# midi_transmitter.net
KiCad netlist of a schematic drawn in EAGLE
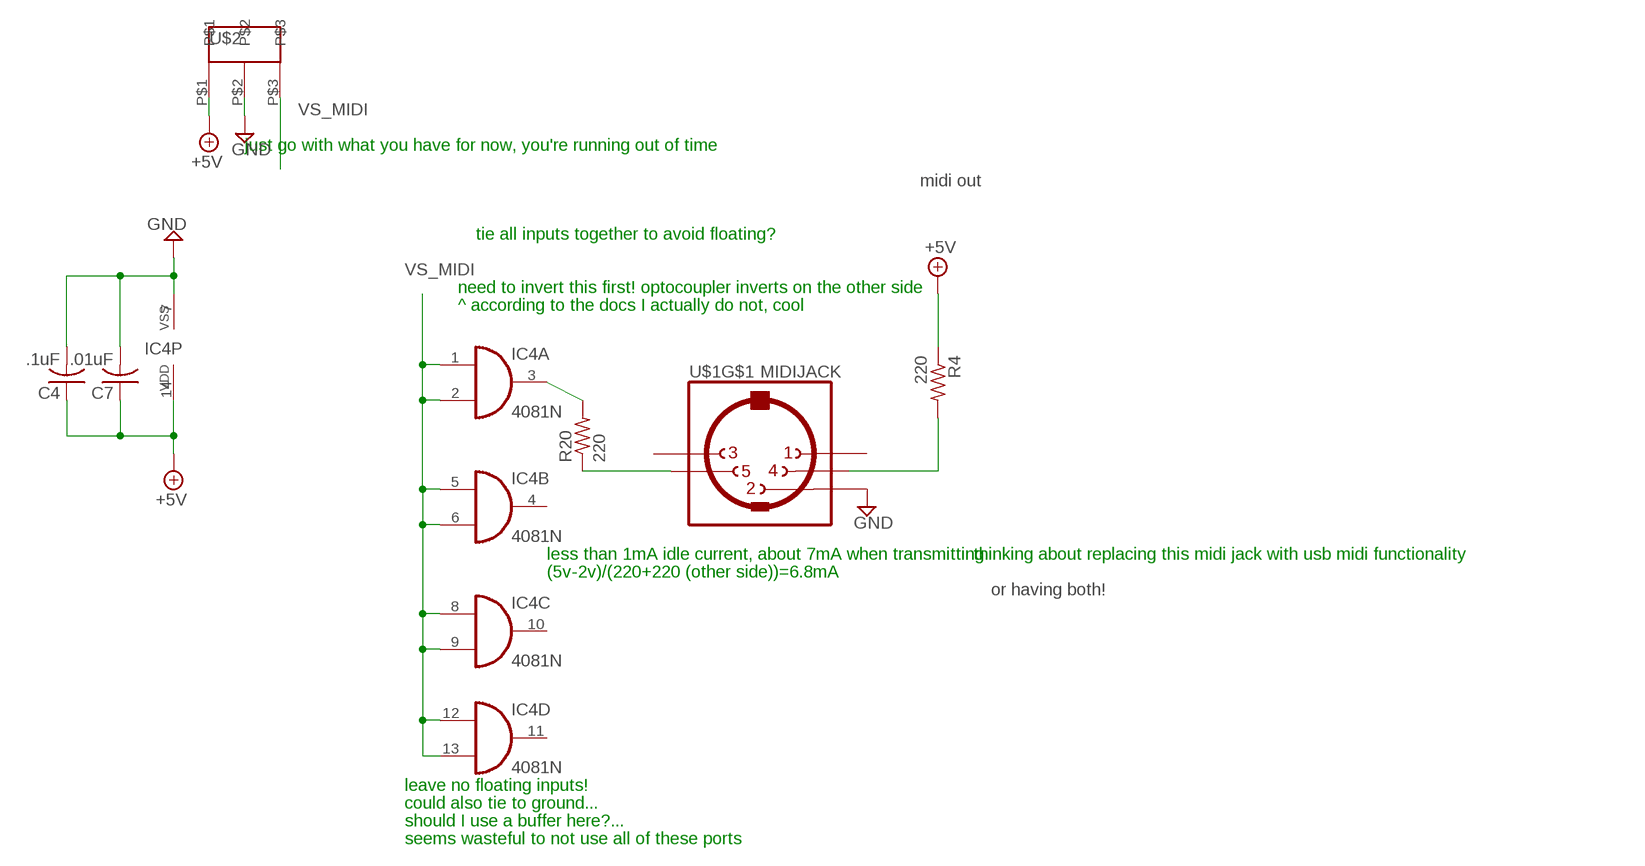
[diagram p0: schematic, sheet 1]

(export (version "E")
  (design (tool "Eeschema 10.0.6"))
  (components
    (comp (ref "C4")
      (value ".1uF")
      (footprint "eagle-import:C025-030X050")
      (libsource (lib "eagle-import") (part "C-US025-030X050"))
    )
    (comp (ref "C7")
      (value ".01uF")
      (footprint "eagle-import:C025-030X050")
      (libsource (lib "eagle-import") (part "C-US025-030X050"))
    )
    (comp (ref "IC4")
      (value "4081N")
      (footprint "eagle-import:DIL14")
      (fields (field (name "SPICEPREFIX") "J"))
      (libsource (lib "eagle-import") (part "4081N"))
    )
    (comp (ref "R4")
      (value "220")
      (footprint "eagle-import:0204_7")
      (libsource (lib "eagle-import") (part "R-US_0204/7"))
    )
    (comp (ref "R20")
      (value "220")
      (footprint "eagle-import:0204_7")
      (libsource (lib "eagle-import") (part "R-US_0204/7"))
    )
    (comp (ref "U$1")
      (value "MIDIJACK")
      (footprint "eagle-import:CP-2350")
      (libsource (lib "eagle-import") (part "MIDIJACK"))
    )
    (comp (ref "U$2")
      (value "3-PIN-HEADER")
      (footprint "eagle-import:3-PIN-HEADER")
      (libsource (lib "eagle-import") (part "3-PIN-HEADER"))
    )
  )
  (nets
    (net (code "1") (name "+5V") (class "Default")
      (node (ref "C4") (pin "1") (pinfunction "1_1") (pintype "passive"))
      (node (ref "C7") (pin "1") (pinfunction "1_1") (pintype "passive"))
      (node (ref "IC4") (pin "14") (pinfunction "VDD_14") (pintype "power_in"))
      (node (ref "R4") (pin "1") (pinfunction "1_1") (pintype "passive"))
      (node (ref "U$2") (pin "P$1") (pinfunction "P$1_P$1") (pintype "bidirectional"))
    )
    (net (code "2") (name "/VS_MIDI") (class "Default")
      (node (ref "IC4") (pin "1") (pinfunction "I0_1") (pintype "input"))
      (node (ref "IC4") (pin "12") (pinfunction "I0_12") (pintype "input"))
      (node (ref "IC4") (pin "13") (pinfunction "I1_13") (pintype "input"))
      (node (ref "IC4") (pin "2") (pinfunction "I1_2") (pintype "input"))
      (node (ref "IC4") (pin "5") (pinfunction "I0_5") (pintype "input"))
      (node (ref "IC4") (pin "6") (pinfunction "I1_6") (pintype "input"))
      (node (ref "IC4") (pin "8") (pinfunction "I0_8") (pintype "input"))
      (node (ref "IC4") (pin "9") (pinfunction "I1_9") (pintype "input"))
      (node (ref "U$2") (pin "P$3") (pinfunction "P$3_P$3") (pintype "bidirectional"))
    )
    (net (code "3") (name "GND") (class "Default")
      (node (ref "C4") (pin "2") (pinfunction "2_2") (pintype "passive"))
      (node (ref "C7") (pin "2") (pinfunction "2_2") (pintype "passive"))
      (node (ref "IC4") (pin "7") (pinfunction "VSS_7") (pintype "power_in"))
      (node (ref "U$1") (pin "2") (pinfunction "2_2") (pintype "passive"))
      (node (ref "U$2") (pin "P$2") (pinfunction "P$2_P$2") (pintype "bidirectional"))
    )
    (net (code "4") (name "Net-(IC4A-O)") (class "Default")
      (node (ref "IC4") (pin "3") (pinfunction "O_3") (pintype "output"))
      (node (ref "R20") (pin "2") (pinfunction "2_2") (pintype "passive"))
    )
    (net (code "5") (name "Net-(R4-Pad2)") (class "Default")
      (node (ref "R4") (pin "2") (pinfunction "2_2") (pintype "passive"))
      (node (ref "U$1") (pin "4") (pinfunction "4_4") (pintype "passive"))
    )
    (net (code "6") (name "Net-(R20-Pad1)") (class "Default")
      (node (ref "R20") (pin "1") (pinfunction "1_1") (pintype "passive"))
      (node (ref "U$1") (pin "5") (pinfunction "5_5") (pintype "passive"))
    )
    (net (code "7") (name "unconnected-(IC4B-O-Pad4)") (class "Default")
      (node (ref "IC4") (pin "4") (pinfunction "O_4") (pintype "output"))
    )
    (net (code "8") (name "unconnected-(IC4C-O-Pad10)") (class "Default")
      (node (ref "IC4") (pin "10") (pinfunction "O_10") (pintype "output"))
    )
    (net (code "9") (name "unconnected-(IC4D-O-Pad11)") (class "Default")
      (node (ref "IC4") (pin "11") (pinfunction "O_11") (pintype "output"))
    )
    (net (code "10") (name "unconnected-(U$1-Pad1)") (class "Default")
      (node (ref "U$1") (pin "1") (pinfunction "1_1") (pintype "passive"))
    )
    (net (code "11") (name "unconnected-(U$1-Pad3)") (class "Default")
      (node (ref "U$1") (pin "3") (pinfunction "3_3") (pintype "passive"))
    )
  )
)
